# Controller_2.net
KiCad netlist of a schematic drawn in Altium Designer
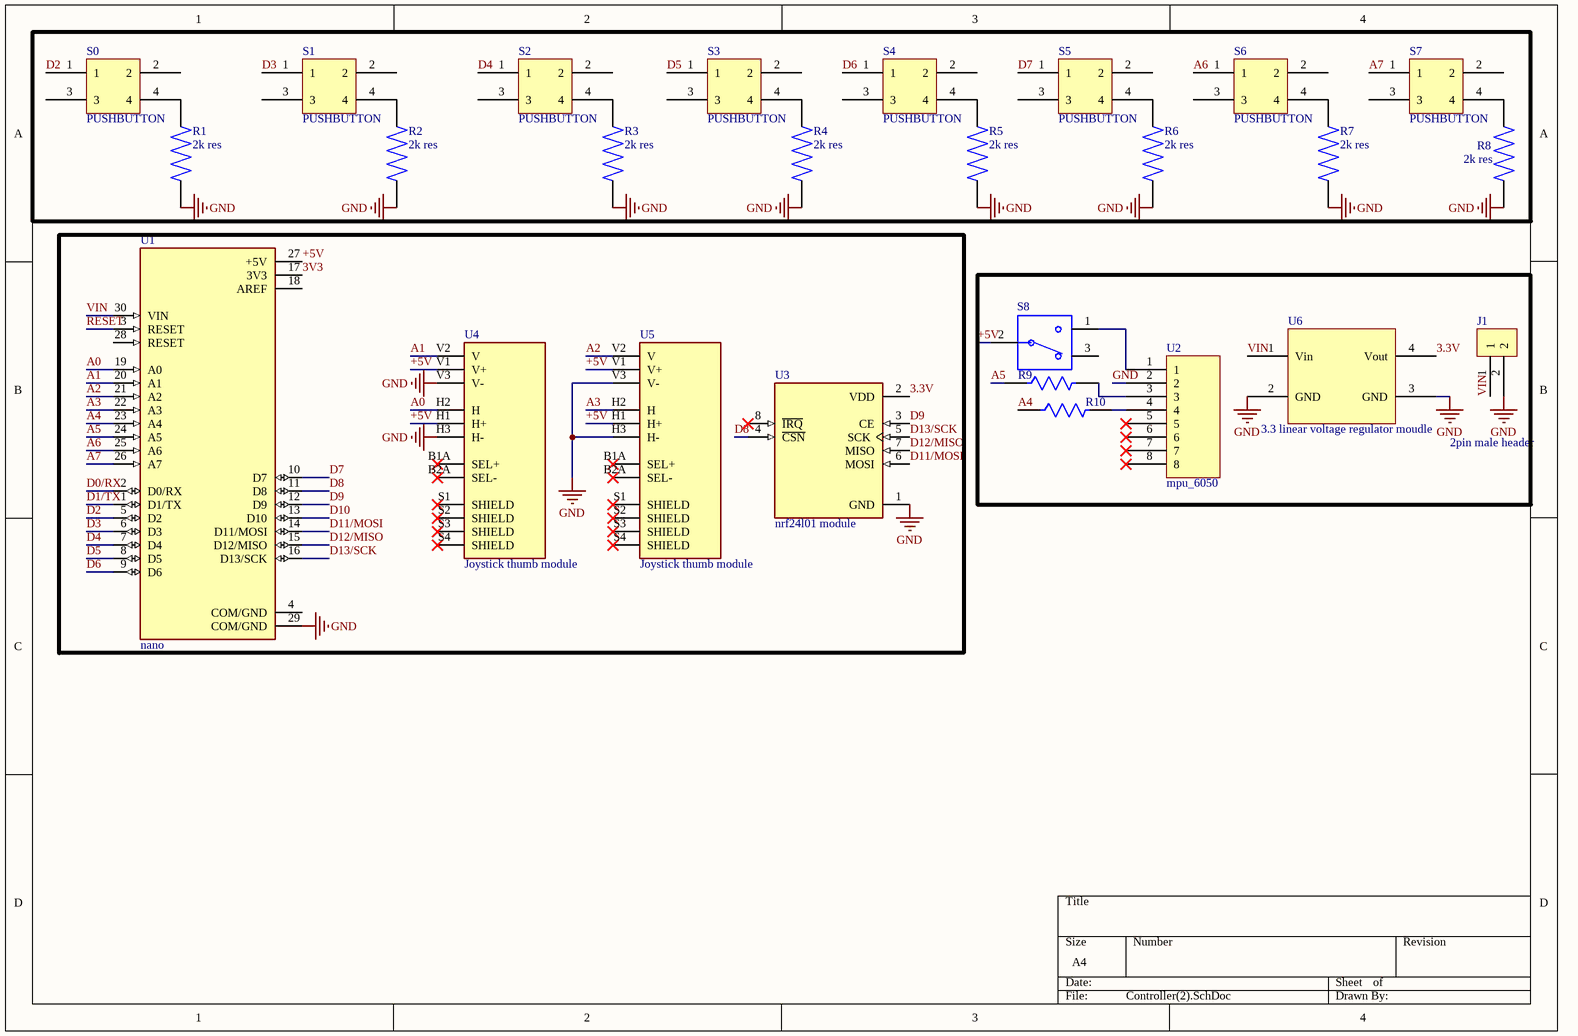
[diagram p0: Controller(2).SchDoc]

(export (version "E")
  (design (tool "Eeschema 10.0.6"))
  (components
    (comp (ref "J1")
      (value "2pin male header")
      (footprint "Controller:2pin")
      (libsource (lib "Controller") (part "2pin"))
    )
    (comp (ref "R1")
      (value "2k res")
      (footprint "Controller:1k res")
      (libsource (lib "Controller") (part "1k res"))
    )
    (comp (ref "R2")
      (value "2k res")
      (footprint "Controller:1k res")
      (libsource (lib "Controller") (part "1k res"))
    )
    (comp (ref "R3")
      (value "2k res")
      (footprint "Controller:1k res")
      (libsource (lib "Controller") (part "1k res"))
    )
    (comp (ref "R4")
      (value "2k res")
      (footprint "Controller:1k res")
      (libsource (lib "Controller") (part "1k res"))
    )
    (comp (ref "R5")
      (value "2k res")
      (footprint "Controller:1k res")
      (libsource (lib "Controller") (part "1k res"))
    )
    (comp (ref "R6")
      (value "2k res")
      (footprint "Controller:1k res")
      (libsource (lib "Controller") (part "1k res"))
    )
    (comp (ref "R7")
      (value "2k res")
      (footprint "Controller:1k res")
      (libsource (lib "Controller") (part "1k res"))
    )
    (comp (ref "R8")
      (value "2k res")
      (footprint "Controller:1k res")
      (libsource (lib "Controller") (part "1k res"))
    )
    (comp (ref "R9")
      (value "10k ohm resistor")
      (footprint "Controller:10k res")
      (libsource (lib "Controller") (part "10k res"))
    )
    (comp (ref "R10")
      (value "10k ohm resistor")
      (footprint "Controller:10k res")
      (libsource (lib "Controller") (part "10k res"))
    )
    (comp (ref "S0")
      (value "PUSHBUTTON")
      (footprint "pushbutton")
      (libsource (lib "Controller") (part "PUSHBUTTON"))
    )
    (comp (ref "S1")
      (value "PUSHBUTTON")
      (footprint "pushbutton")
      (libsource (lib "Controller") (part "PUSHBUTTON"))
    )
    (comp (ref "S2")
      (value "PUSHBUTTON")
      (footprint "pushbutton")
      (libsource (lib "Controller") (part "PUSHBUTTON"))
    )
    (comp (ref "S3")
      (value "PUSHBUTTON")
      (footprint "pushbutton")
      (libsource (lib "Controller") (part "PUSHBUTTON"))
    )
    (comp (ref "S4")
      (value "PUSHBUTTON")
      (footprint "pushbutton")
      (libsource (lib "Controller") (part "PUSHBUTTON"))
    )
    (comp (ref "S5")
      (value "PUSHBUTTON")
      (footprint "pushbutton")
      (libsource (lib "Controller") (part "PUSHBUTTON"))
    )
    (comp (ref "S6")
      (value "PUSHBUTTON")
      (footprint "pushbutton")
      (libsource (lib "Controller") (part "PUSHBUTTON"))
    )
    (comp (ref "S7")
      (value "PUSHBUTTON")
      (footprint "pushbutton")
      (libsource (lib "Controller") (part "PUSHBUTTON"))
    )
    (comp (ref "S8")
      (value "Slide Switch")
      (footprint "Controller:slide_switch")
      (libsource (lib "Controller") (part "slide_switch"))
    )
    (comp (ref "U1")
      (value "nano")
      (footprint "Controller:nano")
      (libsource (lib "Controller") (part "nano"))
    )
    (comp (ref "U2")
      (value "mpu_6050")
      (footprint "Controller:MPU_6050")
      (libsource (lib "Controller") (part "mpu_6050"))
    )
    (comp (ref "U3")
      (value "nrf24l01 module")
      (footprint "Controller:NRF24L01_1")
      (libsource (lib "Controller") (part "nrf24l01"))
    )
    (comp (ref "U4")
      (value "Joystick thumb module")
      (footprint "Joystick_9050")
      (libsource (lib "Controller") (part "Joystick_9050"))
    )
    (comp (ref "U5")
      (value "Joystick thumb module")
      (footprint "Joystick_9050")
      (libsource (lib "Controller") (part "Joystick_9050"))
    )
    (comp (ref "U6")
      (value "3.3 linear voltage regulator moudle")
      (footprint "Controller:ams1117_module")
      (libsource (lib "Controller") (part "am1117_module"))
    )
  )
  (nets
    (net (code "1") (name "/+5V") (class "Default")
      (node (ref "S8") (pin "2") (pinfunction "2_2") (pintype "passive"))
      (node (ref "U1") (pin "27") (pinfunction "+5V_27") (pintype "power_in"))
      (node (ref "U4") (pin "H1") (pinfunction "H+_H1") (pintype "passive"))
      (node (ref "U4") (pin "V1") (pinfunction "V+_V1") (pintype "passive"))
      (node (ref "U5") (pin "H1") (pinfunction "H+_H1") (pintype "passive"))
      (node (ref "U5") (pin "V1") (pinfunction "V+_V1") (pintype "passive"))
    )
    (net (code "2") (name "/3.3V") (class "Default")
      (node (ref "U3") (pin "2") (pinfunction "VDD_2") (pintype "power_in"))
      (node (ref "U6") (pin "4") (pinfunction "Vout_4") (pintype "passive"))
    )
    (net (code "3") (name "/3V3") (class "Default")
      (node (ref "U1") (pin "17") (pinfunction "3V3_17") (pintype "power_in"))
    )
    (net (code "4") (name "/A0") (class "Default")
      (node (ref "U1") (pin "19") (pinfunction "A0_19") (pintype "input"))
      (node (ref "U4") (pin "H2") (pinfunction "H_H2") (pintype "passive"))
    )
    (net (code "5") (name "/A1") (class "Default")
      (node (ref "U1") (pin "20") (pinfunction "A1_20") (pintype "input"))
      (node (ref "U4") (pin "V2") (pinfunction "V_V2") (pintype "passive"))
    )
    (net (code "6") (name "/A2") (class "Default")
      (node (ref "U1") (pin "21") (pinfunction "A2_21") (pintype "input"))
      (node (ref "U5") (pin "V2") (pinfunction "V_V2") (pintype "passive"))
    )
    (net (code "7") (name "/A3") (class "Default")
      (node (ref "U1") (pin "22") (pinfunction "A3_22") (pintype "input"))
      (node (ref "U5") (pin "H2") (pinfunction "H_H2") (pintype "passive"))
    )
    (net (code "8") (name "/A4") (class "Default")
      (node (ref "R10") (pin "1") (pinfunction "1_1") (pintype "passive"))
      (node (ref "U1") (pin "23") (pinfunction "A4_23") (pintype "input"))
    )
    (net (code "9") (name "/A5") (class "Default")
      (node (ref "R9") (pin "1") (pinfunction "1_1") (pintype "passive"))
      (node (ref "U1") (pin "24") (pinfunction "A5_24") (pintype "input"))
    )
    (net (code "10") (name "/A6") (class "Default")
      (node (ref "S6") (pin "1") (pinfunction "1_1") (pintype "passive"))
      (node (ref "U1") (pin "25") (pinfunction "A6_25") (pintype "input"))
    )
    (net (code "11") (name "/A7") (class "Default")
      (node (ref "S7") (pin "1") (pinfunction "1_1") (pintype "passive"))
      (node (ref "U1") (pin "26") (pinfunction "A7_26") (pintype "input"))
    )
    (net (code "12") (name "/D0{slash}RX") (class "Default")
      (node (ref "U1") (pin "2") (pinfunction "D0/RX_2") (pintype "bidirectional"))
    )
    (net (code "13") (name "/D1{slash}TX") (class "Default")
      (node (ref "U1") (pin "1") (pinfunction "D1/TX_1") (pintype "bidirectional"))
    )
    (net (code "14") (name "/D2") (class "Default")
      (node (ref "S0") (pin "1") (pinfunction "1_1") (pintype "passive"))
      (node (ref "U1") (pin "5") (pinfunction "D2_5") (pintype "bidirectional"))
    )
    (net (code "15") (name "/D3") (class "Default")
      (node (ref "S1") (pin "1") (pinfunction "1_1") (pintype "passive"))
      (node (ref "U1") (pin "6") (pinfunction "D3_6") (pintype "bidirectional"))
    )
    (net (code "16") (name "/D4") (class "Default")
      (node (ref "S2") (pin "1") (pinfunction "1_1") (pintype "passive"))
      (node (ref "U1") (pin "7") (pinfunction "D4_7") (pintype "bidirectional"))
    )
    (net (code "17") (name "/D5") (class "Default")
      (node (ref "S3") (pin "1") (pinfunction "1_1") (pintype "passive"))
      (node (ref "U1") (pin "8") (pinfunction "D5_8") (pintype "bidirectional"))
    )
    (net (code "18") (name "/D6") (class "Default")
      (node (ref "S4") (pin "1") (pinfunction "1_1") (pintype "passive"))
      (node (ref "U1") (pin "9") (pinfunction "D6_9") (pintype "bidirectional"))
    )
    (net (code "19") (name "/D7") (class "Default")
      (node (ref "S5") (pin "1") (pinfunction "1_1") (pintype "passive"))
      (node (ref "U1") (pin "10") (pinfunction "D7_10") (pintype "bidirectional"))
    )
    (net (code "20") (name "/D8") (class "Default")
      (node (ref "U1") (pin "11") (pinfunction "D8_11") (pintype "bidirectional"))
      (node (ref "U3") (pin "4") (pinfunction "~{CSN}_4") (pintype "input"))
    )
    (net (code "21") (name "/D9") (class "Default")
      (node (ref "U1") (pin "12") (pinfunction "D9_12") (pintype "bidirectional"))
      (node (ref "U3") (pin "3") (pinfunction "CE_3") (pintype "input"))
    )
    (net (code "22") (name "/D10") (class "Default")
      (node (ref "U1") (pin "13") (pinfunction "D10_13") (pintype "bidirectional"))
    )
    (net (code "23") (name "/D11{slash}MOSI") (class "Default")
      (node (ref "U1") (pin "14") (pinfunction "D11/MOSI_14") (pintype "bidirectional"))
      (node (ref "U3") (pin "6") (pinfunction "MOSI_6") (pintype "input"))
    )
    (net (code "24") (name "/D12{slash}MISO") (class "Default")
      (node (ref "U1") (pin "15") (pinfunction "D12/MISO_15") (pintype "bidirectional"))
      (node (ref "U3") (pin "7") (pinfunction "MISO_7") (pintype "input"))
    )
    (net (code "25") (name "/D13{slash}SCK") (class "Default")
      (node (ref "U1") (pin "16") (pinfunction "D13/SCK_16") (pintype "bidirectional"))
      (node (ref "U3") (pin "5") (pinfunction "SCK_5") (pintype "input"))
    )
    (net (code "26") (name "/RESET") (class "Default")
      (node (ref "U1") (pin "3") (pinfunction "RESET_3") (pintype "input"))
    )
    (net (code "27") (name "/VIN") (class "Default")
      (node (ref "J1") (pin "1") (pinfunction "1_1") (pintype "passive"))
      (node (ref "U1") (pin "30") (pinfunction "VIN_30") (pintype "input"))
      (node (ref "U6") (pin "1") (pinfunction "Vin_1") (pintype "passive"))
    )
    (net (code "28") (name "GND") (class "Default")
      (node (ref "J1") (pin "2") (pinfunction "2_2") (pintype "passive"))
      (node (ref "R1") (pin "2") (pinfunction "2_2") (pintype "passive"))
      (node (ref "R2") (pin "2") (pinfunction "2_2") (pintype "passive"))
      (node (ref "R3") (pin "2") (pinfunction "2_2") (pintype "passive"))
      (node (ref "R4") (pin "2") (pinfunction "2_2") (pintype "passive"))
      (node (ref "R5") (pin "2") (pinfunction "2_2") (pintype "passive"))
      (node (ref "R6") (pin "2") (pinfunction "2_2") (pintype "passive"))
      (node (ref "R7") (pin "2") (pinfunction "2_2") (pintype "passive"))
      (node (ref "R8") (pin "2") (pinfunction "2_2") (pintype "passive"))
      (node (ref "U1") (pin "29") (pinfunction "COM/GND_29") (pintype "power_in"))
      (node (ref "U2") (pin "2") (pinfunction "2_2") (pintype "passive"))
      (node (ref "U3") (pin "1") (pinfunction "GND_1") (pintype "power_in"))
      (node (ref "U4") (pin "H3") (pinfunction "H-_H3") (pintype "passive"))
      (node (ref "U4") (pin "V3") (pinfunction "V-_V3") (pintype "passive"))
      (node (ref "U5") (pin "H3") (pinfunction "H-_H3") (pintype "passive"))
      (node (ref "U5") (pin "V3") (pinfunction "V-_V3") (pintype "passive"))
      (node (ref "U6") (pin "2") (pinfunction "GND_2") (pintype "passive"))
      (node (ref "U6") (pin "3") (pinfunction "GND_3") (pintype "passive"))
    )
    (net (code "29") (name "Net-(R1-Pad1)") (class "Default")
      (node (ref "R1") (pin "1") (pinfunction "1_1") (pintype "passive"))
      (node (ref "S0") (pin "4") (pinfunction "4_4") (pintype "passive"))
    )
    (net (code "30") (name "Net-(R2-Pad1)") (class "Default")
      (node (ref "R2") (pin "1") (pinfunction "1_1") (pintype "passive"))
      (node (ref "S1") (pin "4") (pinfunction "4_4") (pintype "passive"))
    )
    (net (code "31") (name "Net-(R3-Pad1)") (class "Default")
      (node (ref "R3") (pin "1") (pinfunction "1_1") (pintype "passive"))
      (node (ref "S2") (pin "4") (pinfunction "4_4") (pintype "passive"))
    )
    (net (code "32") (name "Net-(R4-Pad1)") (class "Default")
      (node (ref "R4") (pin "1") (pinfunction "1_1") (pintype "passive"))
      (node (ref "S3") (pin "4") (pinfunction "4_4") (pintype "passive"))
    )
    (net (code "33") (name "Net-(R5-Pad1)") (class "Default")
      (node (ref "R5") (pin "1") (pinfunction "1_1") (pintype "passive"))
      (node (ref "S4") (pin "4") (pinfunction "4_4") (pintype "passive"))
    )
    (net (code "34") (name "Net-(R6-Pad1)") (class "Default")
      (node (ref "R6") (pin "1") (pinfunction "1_1") (pintype "passive"))
      (node (ref "S5") (pin "4") (pinfunction "4_4") (pintype "passive"))
    )
    (net (code "35") (name "Net-(R7-Pad1)") (class "Default")
      (node (ref "R7") (pin "1") (pinfunction "1_1") (pintype "passive"))
      (node (ref "S6") (pin "4") (pinfunction "4_4") (pintype "passive"))
    )
    (net (code "36") (name "Net-(R8-Pad1)") (class "Default")
      (node (ref "R8") (pin "1") (pinfunction "1_1") (pintype "passive"))
      (node (ref "S7") (pin "4") (pinfunction "4_4") (pintype "passive"))
    )
    (net (code "37") (name "Net-(R9-Pad2)") (class "Default")
      (node (ref "R9") (pin "2") (pinfunction "2_2") (pintype "passive"))
      (node (ref "U2") (pin "3") (pinfunction "3_3") (pintype "passive"))
    )
    (net (code "38") (name "Net-(R10-Pad2)") (class "Default")
      (node (ref "R10") (pin "2") (pinfunction "2_2") (pintype "passive"))
      (node (ref "U2") (pin "4") (pinfunction "4_4") (pintype "passive"))
    )
    (net (code "39") (name "Net-(S8-Pad1)") (class "Default")
      (node (ref "S8") (pin "1") (pinfunction "1_1") (pintype "passive"))
      (node (ref "U2") (pin "1") (pinfunction "1_1") (pintype "passive"))
    )
    (net (code "40") (name "unconnected-(S0-Pad2)") (class "Default")
      (node (ref "S0") (pin "2") (pinfunction "2_2") (pintype "passive"))
    )
    (net (code "41") (name "unconnected-(S0-Pad3)") (class "Default")
      (node (ref "S0") (pin "3") (pinfunction "3_3") (pintype "passive"))
    )
    (net (code "42") (name "unconnected-(S1-Pad2)") (class "Default")
      (node (ref "S1") (pin "2") (pinfunction "2_2") (pintype "passive"))
    )
    (net (code "43") (name "unconnected-(S1-Pad3)") (class "Default")
      (node (ref "S1") (pin "3") (pinfunction "3_3") (pintype "passive"))
    )
    (net (code "44") (name "unconnected-(S2-Pad2)") (class "Default")
      (node (ref "S2") (pin "2") (pinfunction "2_2") (pintype "passive"))
    )
    (net (code "45") (name "unconnected-(S2-Pad3)") (class "Default")
      (node (ref "S2") (pin "3") (pinfunction "3_3") (pintype "passive"))
    )
    (net (code "46") (name "unconnected-(S3-Pad2)") (class "Default")
      (node (ref "S3") (pin "2") (pinfunction "2_2") (pintype "passive"))
    )
    (net (code "47") (name "unconnected-(S3-Pad3)") (class "Default")
      (node (ref "S3") (pin "3") (pinfunction "3_3") (pintype "passive"))
    )
    (net (code "48") (name "unconnected-(S4-Pad2)") (class "Default")
      (node (ref "S4") (pin "2") (pinfunction "2_2") (pintype "passive"))
    )
    (net (code "49") (name "unconnected-(S4-Pad3)") (class "Default")
      (node (ref "S4") (pin "3") (pinfunction "3_3") (pintype "passive"))
    )
    (net (code "50") (name "unconnected-(S5-Pad2)") (class "Default")
      (node (ref "S5") (pin "2") (pinfunction "2_2") (pintype "passive"))
    )
    (net (code "51") (name "unconnected-(S5-Pad3)") (class "Default")
      (node (ref "S5") (pin "3") (pinfunction "3_3") (pintype "passive"))
    )
    (net (code "52") (name "unconnected-(S6-Pad2)") (class "Default")
      (node (ref "S6") (pin "2") (pinfunction "2_2") (pintype "passive"))
    )
    (net (code "53") (name "unconnected-(S6-Pad3)") (class "Default")
      (node (ref "S6") (pin "3") (pinfunction "3_3") (pintype "passive"))
    )
    (net (code "54") (name "unconnected-(S7-Pad2)") (class "Default")
      (node (ref "S7") (pin "2") (pinfunction "2_2") (pintype "passive"))
    )
    (net (code "55") (name "unconnected-(S7-Pad3)") (class "Default")
      (node (ref "S7") (pin "3") (pinfunction "3_3") (pintype "passive"))
    )
    (net (code "56") (name "unconnected-(S8-Pad3)") (class "Default")
      (node (ref "S8") (pin "3") (pinfunction "3_3") (pintype "passive"))
    )
    (net (code "57") (name "unconnected-(U1-AREF-Pad18)") (class "Default")
      (node (ref "U1") (pin "18") (pinfunction "AREF_18") (pintype "power_in"))
    )
    (net (code "58") (name "unconnected-(U1-COM{slash}GND-Pad4)") (class "Default")
      (node (ref "U1") (pin "4") (pinfunction "COM/GND_4") (pintype "power_in"))
    )
    (net (code "59") (name "unconnected-(U1-RESET-Pad28)") (class "Default")
      (node (ref "U1") (pin "28") (pinfunction "RESET_28") (pintype "input"))
    )
    (net (code "60") (name "unconnected-(U2-Pad5)") (class "Default")
      (node (ref "U2") (pin "5") (pinfunction "5_5") (pintype "passive+no_connect"))
    )
    (net (code "61") (name "unconnected-(U2-Pad6)") (class "Default")
      (node (ref "U2") (pin "6") (pinfunction "6_6") (pintype "passive+no_connect"))
    )
    (net (code "62") (name "unconnected-(U2-Pad7)") (class "Default")
      (node (ref "U2") (pin "7") (pinfunction "7_7") (pintype "passive+no_connect"))
    )
    (net (code "63") (name "unconnected-(U2-Pad8)") (class "Default")
      (node (ref "U2") (pin "8") (pinfunction "8_8") (pintype "passive+no_connect"))
    )
    (net (code "64") (name "unconnected-(U3-~{IRQ}-Pad8)") (class "Default")
      (node (ref "U3") (pin "8") (pinfunction "~{IRQ}_8") (pintype "input+no_connect"))
    )
    (net (code "65") (name "unconnected-(U4-SEL+-PadB1A)") (class "Default")
      (node (ref "U4") (pin "B1A") (pinfunction "SEL+_B1A") (pintype "passive+no_connect"))
    )
    (net (code "66") (name "unconnected-(U4-SEL--PadB2A)") (class "Default")
      (node (ref "U4") (pin "B2A") (pinfunction "SEL-_B2A") (pintype "passive+no_connect"))
    )
    (net (code "67") (name "unconnected-(U4-SHIELD-PadS1)") (class "Default")
      (node (ref "U4") (pin "S1") (pinfunction "SHIELD_S1") (pintype "passive+no_connect"))
    )
    (net (code "68") (name "unconnected-(U4-SHIELD-PadS2)") (class "Default")
      (node (ref "U4") (pin "S2") (pinfunction "SHIELD_S2") (pintype "passive+no_connect"))
    )
    (net (code "69") (name "unconnected-(U4-SHIELD-PadS3)") (class "Default")
      (node (ref "U4") (pin "S3") (pinfunction "SHIELD_S3") (pintype "passive+no_connect"))
    )
    (net (code "70") (name "unconnected-(U4-SHIELD-PadS4)") (class "Default")
      (node (ref "U4") (pin "S4") (pinfunction "SHIELD_S4") (pintype "passive+no_connect"))
    )
    (net (code "71") (name "unconnected-(U5-SEL+-PadB1A)") (class "Default")
      (node (ref "U5") (pin "B1A") (pinfunction "SEL+_B1A") (pintype "passive+no_connect"))
    )
    (net (code "72") (name "unconnected-(U5-SEL--PadB2A)") (class "Default")
      (node (ref "U5") (pin "B2A") (pinfunction "SEL-_B2A") (pintype "passive+no_connect"))
    )
    (net (code "73") (name "unconnected-(U5-SHIELD-PadS1)") (class "Default")
      (node (ref "U5") (pin "S1") (pinfunction "SHIELD_S1") (pintype "passive+no_connect"))
    )
    (net (code "74") (name "unconnected-(U5-SHIELD-PadS2)") (class "Default")
      (node (ref "U5") (pin "S2") (pinfunction "SHIELD_S2") (pintype "passive+no_connect"))
    )
    (net (code "75") (name "unconnected-(U5-SHIELD-PadS3)") (class "Default")
      (node (ref "U5") (pin "S3") (pinfunction "SHIELD_S3") (pintype "passive+no_connect"))
    )
    (net (code "76") (name "unconnected-(U5-SHIELD-PadS4)") (class "Default")
      (node (ref "U5") (pin "S4") (pinfunction "SHIELD_S4") (pintype "passive+no_connect"))
    )
  )
)
